# MiniUIOD_AP.net
KiCad netlist of a schematic drawn in Altium Designer
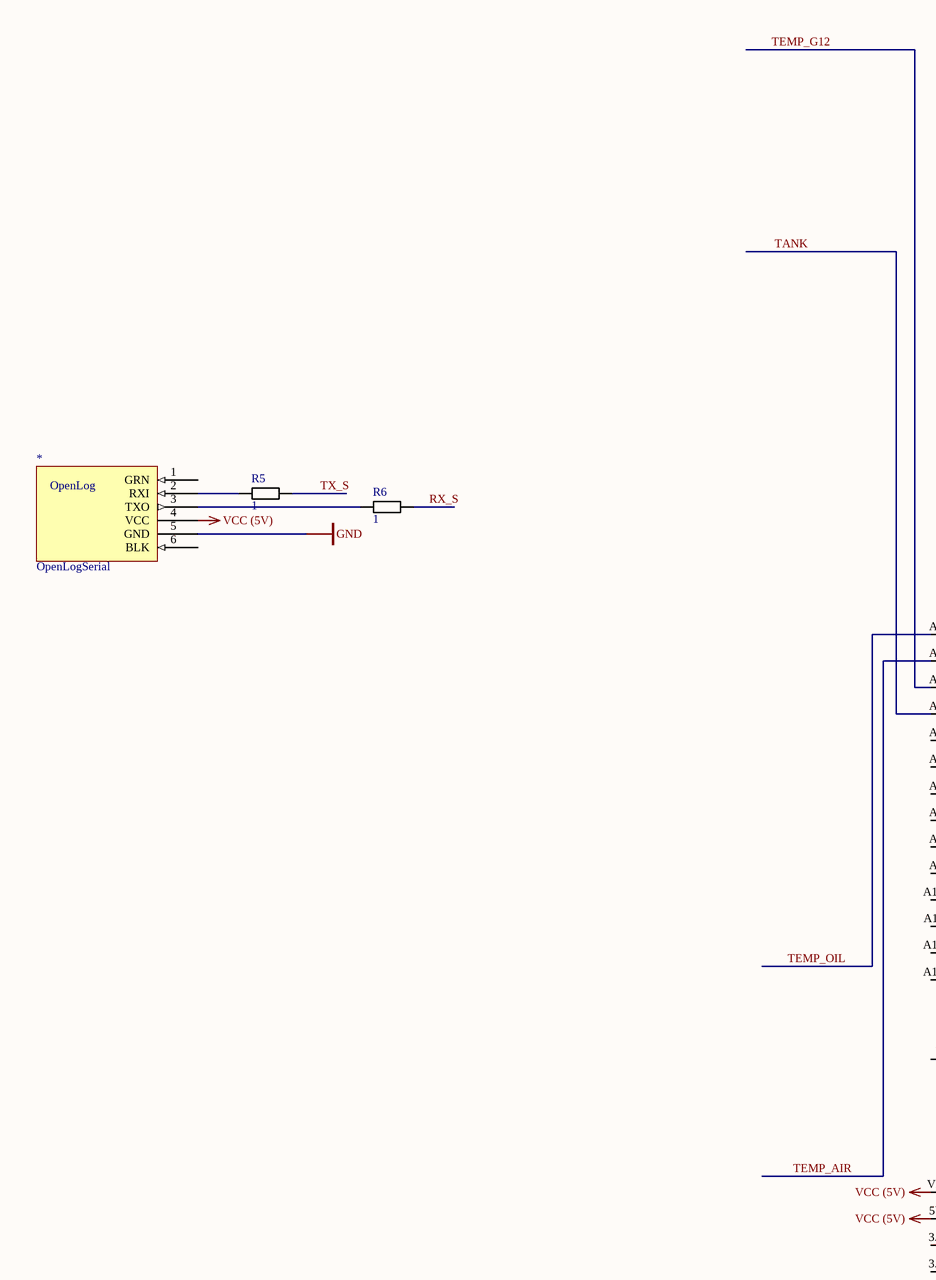
[diagram p0: MiniUIOD_AP.SchDoc, left]
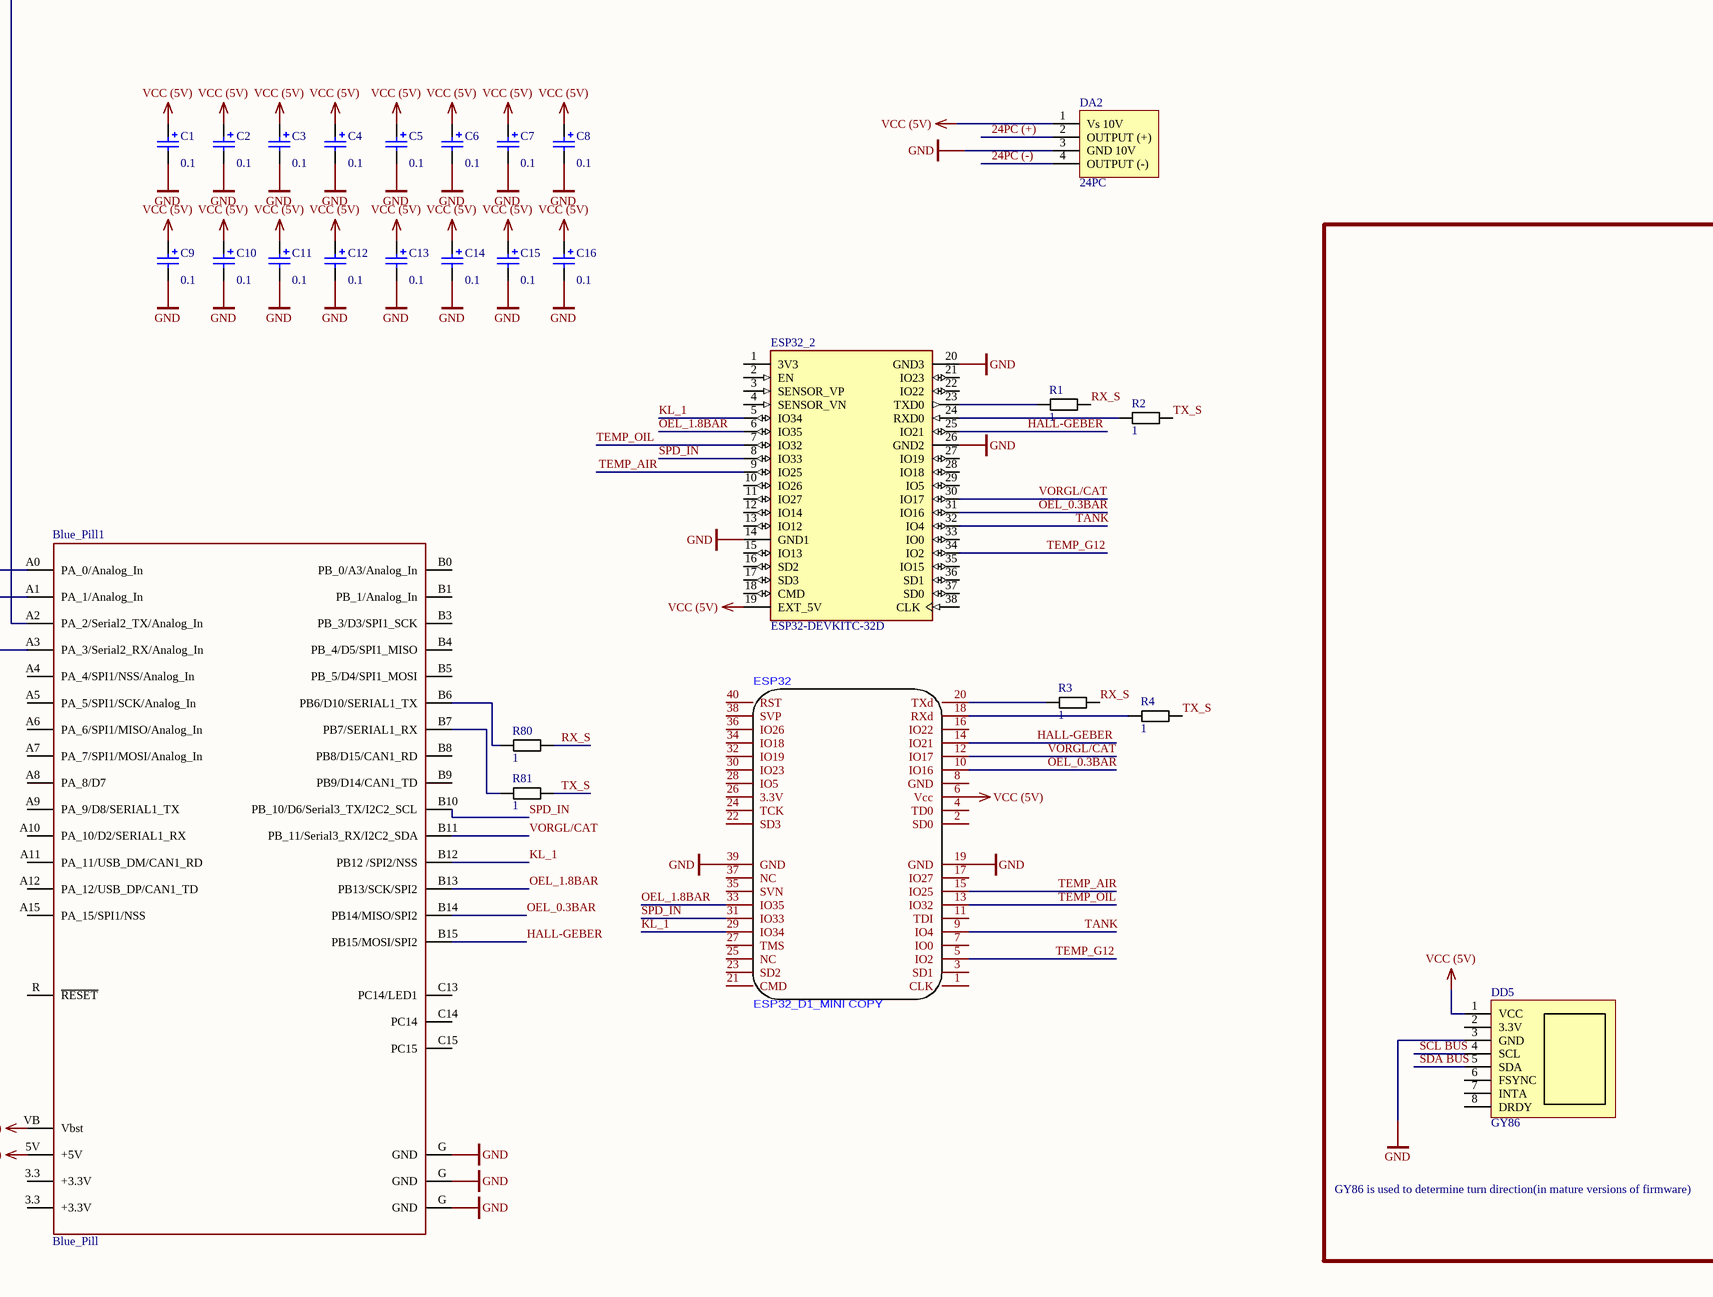
[diagram p1: MiniUIOD_AP.SchDoc, right]

(export (version "E")
  (design (tool "Eeschema 10.0.6"))
  (components
    (comp (ref "*")
      (value "OpenLogSerial")
      (footprint "OpenLogSerial")
      (libsource (lib "SN_NavBoard") (part "OpenLogSerial"))
    )
    (comp (ref "Blue_Pill1")
      (value "Blue_Pill")
      (footprint "BLUE_PILL")
      (libsource (lib "Digifiz_Schlib1") (part "BluePill"))
    )
    (comp (ref "C1")
      (value "0.1")
      (footprint "C0805")
      (description "Polarized Capacitor (Surface Mount)")
      (fields (field (name "Comment") "Cap Pol3") (field (name "PUBLISHER") "Altium Limited"))
      (libsource (lib "Driver_SchLib") (part "Cap Pol3"))
    )
    (comp (ref "C2")
      (value "0.1")
      (footprint "C0805")
      (description "Polarized Capacitor (Surface Mount)")
      (fields (field (name "Comment") "Cap Pol3") (field (name "PUBLISHER") "Altium Limited"))
      (libsource (lib "Driver_SchLib") (part "Cap Pol3"))
    )
    (comp (ref "C3")
      (value "0.1")
      (footprint "C0805")
      (description "Polarized Capacitor (Surface Mount)")
      (fields (field (name "Comment") "Cap Pol3") (field (name "PUBLISHER") "Altium Limited"))
      (libsource (lib "Driver_SchLib") (part "Cap Pol3"))
    )
    (comp (ref "C4")
      (value "0.1")
      (footprint "C0805")
      (description "Polarized Capacitor (Surface Mount)")
      (fields (field (name "Comment") "Cap Pol3") (field (name "PUBLISHER") "Altium Limited"))
      (libsource (lib "Driver_SchLib") (part "Cap Pol3"))
    )
    (comp (ref "C5")
      (value "0.1")
      (footprint "C0805")
      (description "Polarized Capacitor (Surface Mount)")
      (fields (field (name "Comment") "Cap Pol3") (field (name "PUBLISHER") "Altium Limited"))
      (libsource (lib "Driver_SchLib") (part "Cap Pol3"))
    )
    (comp (ref "C6")
      (value "0.1")
      (footprint "C0805")
      (description "Polarized Capacitor (Surface Mount)")
      (fields (field (name "Comment") "Cap Pol3") (field (name "PUBLISHER") "Altium Limited"))
      (libsource (lib "Driver_SchLib") (part "Cap Pol3"))
    )
    (comp (ref "C7")
      (value "0.1")
      (footprint "C0805")
      (description "Polarized Capacitor (Surface Mount)")
      (fields (field (name "Comment") "Cap Pol3") (field (name "PUBLISHER") "Altium Limited"))
      (libsource (lib "Driver_SchLib") (part "Cap Pol3"))
    )
    (comp (ref "C8")
      (value "0.1")
      (footprint "C0805")
      (description "Polarized Capacitor (Surface Mount)")
      (fields (field (name "Comment") "Cap Pol3") (field (name "PUBLISHER") "Altium Limited"))
      (libsource (lib "Driver_SchLib") (part "Cap Pol3"))
    )
    (comp (ref "C9")
      (value "0.1")
      (footprint "C0805")
      (description "Polarized Capacitor (Surface Mount)")
      (fields (field (name "Comment") "Cap Pol3") (field (name "PUBLISHER") "Altium Limited"))
      (libsource (lib "Driver_SchLib") (part "Cap Pol3"))
    )
    (comp (ref "C10")
      (value "0.1")
      (footprint "C0805")
      (description "Polarized Capacitor (Surface Mount)")
      (fields (field (name "Comment") "Cap Pol3") (field (name "PUBLISHER") "Altium Limited"))
      (libsource (lib "Driver_SchLib") (part "Cap Pol3"))
    )
    (comp (ref "C11")
      (value "0.1")
      (footprint "C0805")
      (description "Polarized Capacitor (Surface Mount)")
      (fields (field (name "Comment") "Cap Pol3") (field (name "PUBLISHER") "Altium Limited"))
      (libsource (lib "Driver_SchLib") (part "Cap Pol3"))
    )
    (comp (ref "C12")
      (value "0.1")
      (footprint "C0805")
      (description "Polarized Capacitor (Surface Mount)")
      (fields (field (name "Comment") "Cap Pol3") (field (name "PUBLISHER") "Altium Limited"))
      (libsource (lib "Driver_SchLib") (part "Cap Pol3"))
    )
    (comp (ref "C13")
      (value "0.1")
      (footprint "C0805")
      (description "Polarized Capacitor (Surface Mount)")
      (fields (field (name "Comment") "Cap Pol3") (field (name "PUBLISHER") "Altium Limited"))
      (libsource (lib "Driver_SchLib") (part "Cap Pol3"))
    )
    (comp (ref "C14")
      (value "0.1")
      (footprint "C0805")
      (description "Polarized Capacitor (Surface Mount)")
      (fields (field (name "Comment") "Cap Pol3") (field (name "PUBLISHER") "Altium Limited"))
      (libsource (lib "Driver_SchLib") (part "Cap Pol3"))
    )
    (comp (ref "C15")
      (value "0.1")
      (footprint "C0805")
      (description "Polarized Capacitor (Surface Mount)")
      (fields (field (name "Comment") "Cap Pol3") (field (name "PUBLISHER") "Altium Limited"))
      (libsource (lib "Driver_SchLib") (part "Cap Pol3"))
    )
    (comp (ref "C16")
      (value "0.1")
      (footprint "C0805")
      (description "Polarized Capacitor (Surface Mount)")
      (fields (field (name "Comment") "Cap Pol3") (field (name "PUBLISHER") "Altium Limited"))
      (libsource (lib "Driver_SchLib") (part "Cap Pol3"))
    )
    (comp (ref "DA2") (value "24PC") (footprint "24PC") (libsource (lib "Digifiz_Schlib1") (part "24PC")))
    (comp (ref "DD5")
      (value "GY86")
      (footprint "GY86_MODEL")
      (libsource (lib "Digifiz_Schlib1") (part "GY86_MODEL"))
    )
    (comp (ref "ESP32")
      (value "ESP32_D1_MINI COPY")
      (footprint "ESP32_MINI_MHET")
      (libsource (lib "MiniUIOD") (part "ESP32_D1_MINI COPY"))
    )
    (comp (ref "ESP32_2")
      (value "ESP32-DEVKITC-32D")
      (footprint "MODULE_ESP32-DEVKITC-32D")
      (description "EVAL BOARD FOR ESP-WROOM-32")
      (fields (field (name "MF") "Espressif Systems"))
      (libsource (lib "MiniUIOD") (part "ESP32-DEVKITC-32D"))
    )
    (comp (ref "R1")
      (value "1")
      (footprint "SMT0603/VISHAY")
      (libsource (lib "Digifiz_Schlib1") (part "CRCW0603_47"))
    )
    (comp (ref "R2")
      (value "1")
      (footprint "SMT0603/VISHAY")
      (libsource (lib "Digifiz_Schlib1") (part "CRCW0603_47"))
    )
    (comp (ref "R3")
      (value "1")
      (footprint "SMT0603/VISHAY")
      (libsource (lib "Digifiz_Schlib1") (part "CRCW0603_47"))
    )
    (comp (ref "R4")
      (value "1")
      (footprint "SMT0603/VISHAY")
      (libsource (lib "Digifiz_Schlib1") (part "CRCW0603_47"))
    )
    (comp (ref "R5")
      (value "1")
      (footprint "SMT0603/VISHAY")
      (libsource (lib "Digifiz_Schlib1") (part "CRCW0603_47"))
    )
    (comp (ref "R6")
      (value "1")
      (footprint "SMT0603/VISHAY")
      (libsource (lib "Digifiz_Schlib1") (part "CRCW0603_47"))
    )
    (comp (ref "R80")
      (value "1")
      (footprint "SMT0603/VISHAY")
      (libsource (lib "Digifiz_Schlib1") (part "CRCW0603_47"))
    )
    (comp (ref "R81")
      (value "1")
      (footprint "SMT0603/VISHAY")
      (libsource (lib "Digifiz_Schlib1") (part "CRCW0603_47"))
    )
  )
  (nets
    (net (code "1") (name "/24PC (+)") (class "Default")
      (node (ref "DA2") (pin "2") (pinfunction "OUTPUT_(+)_2") (pintype "passive"))
    )
    (net (code "2") (name "/24PC (-)") (class "Default")
      (node (ref "DA2") (pin "4") (pinfunction "OUTPUT_(-)_4") (pintype "passive"))
    )
    (net (code "3") (name "/HALL-GEBER") (class "Default")
      (node (ref "Blue_Pill1") (pin "B15") (pinfunction "PB15/MOSI/SPI2_B15") (pintype "passive"))
      (node (ref "ESP32") (pin "14") (pinfunction "IO21_14") (pintype "passive"))
      (node (ref "ESP32_2") (pin "25") (pinfunction "IO21_25") (pintype "bidirectional"))
    )
    (net (code "4") (name "/KL_1") (class "Default")
      (node (ref "Blue_Pill1") (pin "B12") (pinfunction "PB12_/SPI2/NSS_B12") (pintype "passive"))
      (node (ref "ESP32") (pin "29") (pinfunction "IO34_29") (pintype "passive"))
      (node (ref "ESP32_2") (pin "5") (pinfunction "IO34_5") (pintype "bidirectional"))
    )
    (net (code "5") (name "/OEL_0.3BAR") (class "Default")
      (node (ref "Blue_Pill1") (pin "B14") (pinfunction "PB14/MISO/SPI2_B14") (pintype "passive"))
      (node (ref "ESP32") (pin "10") (pinfunction "IO16_10") (pintype "passive"))
      (node (ref "ESP32_2") (pin "31") (pinfunction "IO16_31") (pintype "bidirectional"))
    )
    (net (code "6") (name "/OEL_1.8BAR") (class "Default")
      (node (ref "Blue_Pill1") (pin "B13") (pinfunction "PB13/SCK/SPI2_B13") (pintype "passive"))
      (node (ref "ESP32") (pin "33") (pinfunction "IO35_33") (pintype "passive"))
      (node (ref "ESP32_2") (pin "6") (pinfunction "IO35_6") (pintype "bidirectional"))
    )
    (net (code "7") (name "/RX_S") (class "Default")
      (node (ref "R1") (pin "1") (pinfunction "1_1") (pintype "passive"))
      (node (ref "R3") (pin "1") (pinfunction "1_1") (pintype "passive"))
      (node (ref "R6") (pin "1") (pinfunction "1_1") (pintype "passive"))
      (node (ref "R80") (pin "1") (pinfunction "1_1") (pintype "passive"))
    )
    (net (code "8") (name "/SCL BUS") (class "Default")
      (node (ref "DD5") (pin "4") (pinfunction "SCL_4") (pintype "passive"))
    )
    (net (code "9") (name "/SDA BUS") (class "Default")
      (node (ref "DD5") (pin "5") (pinfunction "SDA_5") (pintype "passive"))
    )
    (net (code "10") (name "/SPD_IN") (class "Default")
      (node (ref "Blue_Pill1") (pin "B10") (pinfunction "PB_10/D6/Serial3_TX/I2C2_SCL_B10") (pintype "passive"))
      (node (ref "ESP32") (pin "31") (pinfunction "IO33_31") (pintype "passive"))
      (node (ref "ESP32_2") (pin "8") (pinfunction "IO33_8") (pintype "bidirectional"))
    )
    (net (code "11") (name "/TANK") (class "Default")
      (node (ref "Blue_Pill1") (pin "A3") (pinfunction "PA_3/Serial2_RX/Analog_In_A3") (pintype "passive"))
      (node (ref "ESP32") (pin "9") (pinfunction "IO4_9") (pintype "passive"))
      (node (ref "ESP32_2") (pin "32") (pinfunction "IO4_32") (pintype "bidirectional"))
    )
    (net (code "12") (name "/TEMP_AIR") (class "Default")
      (node (ref "Blue_Pill1") (pin "A1") (pinfunction "PA_1/Analog_In_A1") (pintype "passive"))
      (node (ref "ESP32") (pin "15") (pinfunction "IO25_15") (pintype "passive"))
      (node (ref "ESP32_2") (pin "9") (pinfunction "IO25_9") (pintype "bidirectional"))
    )
    (net (code "13") (name "/TEMP_G12") (class "Default")
      (node (ref "Blue_Pill1") (pin "A2") (pinfunction "PA_2/Serial2_TX/Analog_In_A2") (pintype "passive"))
      (node (ref "ESP32") (pin "5") (pinfunction "IO2_5") (pintype "passive"))
      (node (ref "ESP32_2") (pin "34") (pinfunction "IO2_34") (pintype "bidirectional"))
    )
    (net (code "14") (name "/TEMP_OIL") (class "Default")
      (node (ref "Blue_Pill1") (pin "A0") (pinfunction "PA_0/Analog_In_A0") (pintype "passive"))
      (node (ref "ESP32") (pin "13") (pinfunction "IO32_13") (pintype "passive"))
      (node (ref "ESP32_2") (pin "7") (pinfunction "IO32_7") (pintype "bidirectional"))
    )
    (net (code "15") (name "/TX_S") (class "Default")
      (node (ref "R2") (pin "1") (pinfunction "1_1") (pintype "passive"))
      (node (ref "R4") (pin "1") (pinfunction "1_1") (pintype "passive"))
      (node (ref "R5") (pin "1") (pinfunction "1_1") (pintype "passive"))
      (node (ref "R81") (pin "1") (pinfunction "1_1") (pintype "passive"))
    )
    (net (code "16") (name "/VORGL{slash}CAT") (class "Default")
      (node (ref "Blue_Pill1") (pin "B11") (pinfunction "PB_11/Serial3_RX/I2C2_SDA_B11") (pintype "passive"))
      (node (ref "ESP32") (pin "12") (pinfunction "IO17_12") (pintype "passive"))
      (node (ref "ESP32_2") (pin "30") (pinfunction "IO17_30") (pintype "bidirectional"))
    )
    (net (code "17") (name "GND") (class "Default")
      (node (ref "*") (pin "5") (pinfunction "GND_5") (pintype "power_in"))
      (node (ref "Blue_Pill1") (pin "G") (pinfunction "GND_G") (pintype "passive"))
      (node (ref "C1") (pin "2") (pinfunction "2_2") (pintype "passive"))
      (node (ref "C10") (pin "2") (pinfunction "2_2") (pintype "passive"))
      (node (ref "C11") (pin "2") (pinfunction "2_2") (pintype "passive"))
      (node (ref "C12") (pin "2") (pinfunction "2_2") (pintype "passive"))
      (node (ref "C13") (pin "2") (pinfunction "2_2") (pintype "passive"))
      (node (ref "C14") (pin "2") (pinfunction "2_2") (pintype "passive"))
      (node (ref "C15") (pin "2") (pinfunction "2_2") (pintype "passive"))
      (node (ref "C16") (pin "2") (pinfunction "2_2") (pintype "passive"))
      (node (ref "C2") (pin "2") (pinfunction "2_2") (pintype "passive"))
      (node (ref "C3") (pin "2") (pinfunction "2_2") (pintype "passive"))
      (node (ref "C4") (pin "2") (pinfunction "2_2") (pintype "passive"))
      (node (ref "C5") (pin "2") (pinfunction "2_2") (pintype "passive"))
      (node (ref "C6") (pin "2") (pinfunction "2_2") (pintype "passive"))
      (node (ref "C7") (pin "2") (pinfunction "2_2") (pintype "passive"))
      (node (ref "C8") (pin "2") (pinfunction "2_2") (pintype "passive"))
      (node (ref "C9") (pin "2") (pinfunction "2_2") (pintype "passive"))
      (node (ref "DA2") (pin "3") (pinfunction "GND_10V_3") (pintype "passive"))
      (node (ref "DD5") (pin "3") (pinfunction "GND_3") (pintype "passive"))
      (node (ref "ESP32") (pin "19") (pinfunction "GND_19") (pintype "passive"))
      (node (ref "ESP32") (pin "39") (pinfunction "GND_39") (pintype "passive"))
      (node (ref "ESP32_2") (pin "14") (pinfunction "GND1_14") (pintype "power_in"))
      (node (ref "ESP32_2") (pin "20") (pinfunction "GND3_20") (pintype "power_in"))
      (node (ref "ESP32_2") (pin "26") (pinfunction "GND2_26") (pintype "power_in"))
    )
    (net (code "18") (name "Net-(*-RXI)") (class "Default")
      (node (ref "*") (pin "2") (pinfunction "RXI_2") (pintype "input"))
      (node (ref "R5") (pin "2") (pinfunction "2_2") (pintype "passive"))
    )
    (net (code "19") (name "Net-(*-TXO)") (class "Default")
      (node (ref "*") (pin "3") (pinfunction "TXO_3") (pintype "output"))
      (node (ref "R6") (pin "2") (pinfunction "2_2") (pintype "passive"))
    )
    (net (code "20") (name "Net-(Blue_Pill1-PB6{slash}D10{slash}SERIAL1_TX)") (class "Default")
      (node (ref "Blue_Pill1") (pin "B6") (pinfunction "PB6/D10/SERIAL1_TX_B6") (pintype "passive"))
      (node (ref "R80") (pin "2") (pinfunction "2_2") (pintype "passive"))
    )
    (net (code "21") (name "Net-(Blue_Pill1-PB7{slash}SERIAL1_RX)") (class "Default")
      (node (ref "Blue_Pill1") (pin "B7") (pinfunction "PB7/SERIAL1_RX_B7") (pintype "passive"))
      (node (ref "R81") (pin "2") (pinfunction "2_2") (pintype "passive"))
    )
    (net (code "22") (name "Net-(ESP32-RXd)") (class "Default")
      (node (ref "ESP32") (pin "18") (pinfunction "RXd_18") (pintype "passive"))
      (node (ref "R4") (pin "2") (pinfunction "2_2") (pintype "passive"))
    )
    (net (code "23") (name "Net-(ESP32-TXd)") (class "Default")
      (node (ref "ESP32") (pin "20") (pinfunction "TXd_20") (pintype "passive"))
      (node (ref "R3") (pin "2") (pinfunction "2_2") (pintype "passive"))
    )
    (net (code "24") (name "Net-(ESP32_2-RXD0)") (class "Default")
      (node (ref "ESP32_2") (pin "24") (pinfunction "RXD0_24") (pintype "input"))
      (node (ref "R2") (pin "2") (pinfunction "2_2") (pintype "passive"))
    )
    (net (code "25") (name "Net-(ESP32_2-TXD0)") (class "Default")
      (node (ref "ESP32_2") (pin "23") (pinfunction "TXD0_23") (pintype "output"))
      (node (ref "R1") (pin "2") (pinfunction "2_2") (pintype "passive"))
    )
    (net (code "26") (name "VCC (5V)") (class "Default")
      (node (ref "*") (pin "4") (pinfunction "VCC_4") (pintype "power_in"))
      (node (ref "Blue_Pill1") (pin "5V") (pinfunction "+5V_5V") (pintype "passive"))
      (node (ref "Blue_Pill1") (pin "VB") (pinfunction "Vbst_VB") (pintype "passive"))
      (node (ref "C1") (pin "1") (pinfunction "1_1") (pintype "passive"))
      (node (ref "C10") (pin "1") (pinfunction "1_1") (pintype "passive"))
      (node (ref "C11") (pin "1") (pinfunction "1_1") (pintype "passive"))
      (node (ref "C12") (pin "1") (pinfunction "1_1") (pintype "passive"))
      (node (ref "C13") (pin "1") (pinfunction "1_1") (pintype "passive"))
      (node (ref "C14") (pin "1") (pinfunction "1_1") (pintype "passive"))
      (node (ref "C15") (pin "1") (pinfunction "1_1") (pintype "passive"))
      (node (ref "C16") (pin "1") (pinfunction "1_1") (pintype "passive"))
      (node (ref "C2") (pin "1") (pinfunction "1_1") (pintype "passive"))
      (node (ref "C3") (pin "1") (pinfunction "1_1") (pintype "passive"))
      (node (ref "C4") (pin "1") (pinfunction "1_1") (pintype "passive"))
      (node (ref "C5") (pin "1") (pinfunction "1_1") (pintype "passive"))
      (node (ref "C6") (pin "1") (pinfunction "1_1") (pintype "passive"))
      (node (ref "C7") (pin "1") (pinfunction "1_1") (pintype "passive"))
      (node (ref "C8") (pin "1") (pinfunction "1_1") (pintype "passive"))
      (node (ref "C9") (pin "1") (pinfunction "1_1") (pintype "passive"))
      (node (ref "DA2") (pin "1") (pinfunction "Vs_10V_1") (pintype "passive"))
      (node (ref "DD5") (pin "1") (pinfunction "VCC_1") (pintype "passive"))
      (node (ref "ESP32") (pin "6") (pinfunction "Vcc_6") (pintype "passive"))
      (node (ref "ESP32_2") (pin "19") (pinfunction "EXT_5V_19") (pintype "power_in"))
    )
    (net (code "27") (name "unconnected-(*-BLK-Pad6)") (class "Default")
      (node (ref "*") (pin "6") (pinfunction "BLK_6") (pintype "input"))
    )
    (net (code "28") (name "unconnected-(*-GRN-Pad1)") (class "Default")
      (node (ref "*") (pin "1") (pinfunction "GRN_1") (pintype "input"))
    )
    (net (code "29") (name "unconnected-(Blue_Pill1-+3.3V-Pad3.3)") (class "Default")
      (node (ref "Blue_Pill1") (pin "3.3") (pinfunction "+3.3V_3.3") (pintype "passive"))
    )
    (net (code "30") (name "unconnected-(Blue_Pill1-+3.3V-Pad3.3)_1") (class "Default")
      (node (ref "Blue_Pill1") (pin "3.3") (pinfunction "+3.3V_3.3") (pintype "passive"))
    )
    (net (code "31") (name "unconnected-(Blue_Pill1-PA_4{slash}SPI1{slash}NSS{slash}Analog_In-PadA4)") (class "Default")
      (node (ref "Blue_Pill1") (pin "A4") (pinfunction "PA_4/SPI1/NSS/Analog_In_A4") (pintype "passive"))
    )
    (net (code "32") (name "unconnected-(Blue_Pill1-PA_5{slash}SPI1{slash}SCK{slash}Analog_In-PadA5)") (class "Default")
      (node (ref "Blue_Pill1") (pin "A5") (pinfunction "PA_5/SPI1/SCK/Analog_In_A5") (pintype "passive"))
    )
    (net (code "33") (name "unconnected-(Blue_Pill1-PA_6{slash}SPI1{slash}MISO{slash}Analog_In-PadA6)") (class "Default")
      (node (ref "Blue_Pill1") (pin "A6") (pinfunction "PA_6/SPI1/MISO/Analog_In_A6") (pintype "passive"))
    )
    (net (code "34") (name "unconnected-(Blue_Pill1-PA_7{slash}SPI1{slash}MOSI{slash}Analog_In-PadA7)") (class "Default")
      (node (ref "Blue_Pill1") (pin "A7") (pinfunction "PA_7/SPI1/MOSI/Analog_In_A7") (pintype "passive"))
    )
    (net (code "35") (name "unconnected-(Blue_Pill1-PA_8{slash}D7-PadA8)") (class "Default")
      (node (ref "Blue_Pill1") (pin "A8") (pinfunction "PA_8/D7_A8") (pintype "passive"))
    )
    (net (code "36") (name "unconnected-(Blue_Pill1-PA_9{slash}D8{slash}SERIAL1_TX-PadA9)") (class "Default")
      (node (ref "Blue_Pill1") (pin "A9") (pinfunction "PA_9/D8/SERIAL1_TX_A9") (pintype "passive"))
    )
    (net (code "37") (name "unconnected-(Blue_Pill1-PA_10{slash}D2{slash}SERIAL1_RX-PadA10)") (class "Default")
      (node (ref "Blue_Pill1") (pin "A10") (pinfunction "PA_10/D2/SERIAL1_RX_A10") (pintype "passive"))
    )
    (net (code "38") (name "unconnected-(Blue_Pill1-PA_11{slash}USB_DM{slash}CAN1_RD-PadA11)") (class "Default")
      (node (ref "Blue_Pill1") (pin "A11") (pinfunction "PA_11/USB_DM/CAN1_RD_A11") (pintype "passive"))
    )
    (net (code "39") (name "unconnected-(Blue_Pill1-PA_12{slash}USB_DP{slash}CAN1_TD-PadA12)") (class "Default")
      (node (ref "Blue_Pill1") (pin "A12") (pinfunction "PA_12/USB_DP/CAN1_TD_A12") (pintype "passive"))
    )
    (net (code "40") (name "unconnected-(Blue_Pill1-PA_15{slash}SPI1{slash}NSS-PadA15)") (class "Default")
      (node (ref "Blue_Pill1") (pin "A15") (pinfunction "PA_15/SPI1/NSS_A15") (pintype "passive"))
    )
    (net (code "41") (name "unconnected-(Blue_Pill1-PB8{slash}D15{slash}CAN1_RD-PadB8)") (class "Default")
      (node (ref "Blue_Pill1") (pin "B8") (pinfunction "PB8/D15/CAN1_RD_B8") (pintype "passive"))
    )
    (net (code "42") (name "unconnected-(Blue_Pill1-PB9{slash}D14{slash}CAN1_TD-PadB9)") (class "Default")
      (node (ref "Blue_Pill1") (pin "B9") (pinfunction "PB9/D14/CAN1_TD_B9") (pintype "passive"))
    )
    (net (code "43") (name "unconnected-(Blue_Pill1-PB_0{slash}A3{slash}Analog_In-PadB0)") (class "Default")
      (node (ref "Blue_Pill1") (pin "B0") (pinfunction "PB_0/A3/Analog_In_B0") (pintype "passive"))
    )
    (net (code "44") (name "unconnected-(Blue_Pill1-PB_1{slash}Analog_In-PadB1)") (class "Default")
      (node (ref "Blue_Pill1") (pin "B1") (pinfunction "PB_1/Analog_In_B1") (pintype "passive"))
    )
    (net (code "45") (name "unconnected-(Blue_Pill1-PB_3{slash}D3{slash}SPI1_SCK-PadB3)") (class "Default")
      (node (ref "Blue_Pill1") (pin "B3") (pinfunction "PB_3/D3/SPI1_SCK_B3") (pintype "passive"))
    )
    (net (code "46") (name "unconnected-(Blue_Pill1-PB_4{slash}D5{slash}SPI1_MISO-PadB4)") (class "Default")
      (node (ref "Blue_Pill1") (pin "B4") (pinfunction "PB_4/D5/SPI1_MISO_B4") (pintype "passive"))
    )
    (net (code "47") (name "unconnected-(Blue_Pill1-PB_5{slash}D4{slash}SPI1_MOSI-PadB5)") (class "Default")
      (node (ref "Blue_Pill1") (pin "B5") (pinfunction "PB_5/D4/SPI1_MOSI_B5") (pintype "passive"))
    )
    (net (code "48") (name "unconnected-(Blue_Pill1-PC14-PadC14)") (class "Default")
      (node (ref "Blue_Pill1") (pin "C14") (pinfunction "PC14_C14") (pintype "passive"))
    )
    (net (code "49") (name "unconnected-(Blue_Pill1-PC14{slash}LED1-PadC13)") (class "Default")
      (node (ref "Blue_Pill1") (pin "C13") (pinfunction "PC14/LED1_C13") (pintype "passive"))
    )
    (net (code "50") (name "unconnected-(Blue_Pill1-PC15-PadC15)") (class "Default")
      (node (ref "Blue_Pill1") (pin "C15") (pinfunction "PC15_C15") (pintype "passive"))
    )
    (net (code "51") (name "unconnected-(Blue_Pill1-~{RESET}-PadR)") (class "Default")
      (node (ref "Blue_Pill1") (pin "R") (pinfunction "~{RESET}_R") (pintype "passive"))
    )
    (net (code "52") (name "unconnected-(DD5-3.3V-Pad2)") (class "Default")
      (node (ref "DD5") (pin "2") (pinfunction "3.3V_2") (pintype "passive"))
    )
    (net (code "53") (name "unconnected-(DD5-DRDY-Pad8)") (class "Default")
      (node (ref "DD5") (pin "8") (pinfunction "DRDY_8") (pintype "passive"))
    )
    (net (code "54") (name "unconnected-(DD5-FSYNC-Pad6)") (class "Default")
      (node (ref "DD5") (pin "6") (pinfunction "FSYNC_6") (pintype "passive"))
    )
    (net (code "55") (name "unconnected-(DD5-INTA-Pad7)") (class "Default")
      (node (ref "DD5") (pin "7") (pinfunction "INTA_7") (pintype "passive"))
    )
    (net (code "56") (name "unconnected-(ESP32-3.3V-Pad26)") (class "Default")
      (node (ref "ESP32") (pin "26") (pinfunction "3.3V_26") (pintype "passive"))
    )
    (net (code "57") (name "unconnected-(ESP32-CLK-Pad1)") (class "Default")
      (node (ref "ESP32") (pin "1") (pinfunction "CLK_1") (pintype "passive"))
    )
    (net (code "58") (name "unconnected-(ESP32-CMD-Pad21)") (class "Default")
      (node (ref "ESP32") (pin "21") (pinfunction "CMD_21") (pintype "passive"))
    )
    (net (code "59") (name "unconnected-(ESP32-GND-Pad8)") (class "Default")
      (node (ref "ESP32") (pin "8") (pinfunction "GND_8") (pintype "passive"))
    )
    (net (code "60") (name "unconnected-(ESP32-IO0-Pad7)") (class "Default")
      (node (ref "ESP32") (pin "7") (pinfunction "IO0_7") (pintype "passive"))
    )
    (net (code "61") (name "unconnected-(ESP32-IO5-Pad28)") (class "Default")
      (node (ref "ESP32") (pin "28") (pinfunction "IO5_28") (pintype "passive"))
    )
    (net (code "62") (name "unconnected-(ESP32-IO18-Pad34)") (class "Default")
      (node (ref "ESP32") (pin "34") (pinfunction "IO18_34") (pintype "passive"))
    )
    (net (code "63") (name "unconnected-(ESP32-IO19-Pad32)") (class "Default")
      (node (ref "ESP32") (pin "32") (pinfunction "IO19_32") (pintype "passive"))
    )
    (net (code "64") (name "unconnected-(ESP32-IO22-Pad16)") (class "Default")
      (node (ref "ESP32") (pin "16") (pinfunction "IO22_16") (pintype "passive"))
    )
    (net (code "65") (name "unconnected-(ESP32-IO23-Pad30)") (class "Default")
      (node (ref "ESP32") (pin "30") (pinfunction "IO23_30") (pintype "passive"))
    )
    (net (code "66") (name "unconnected-(ESP32-IO26-Pad36)") (class "Default")
      (node (ref "ESP32") (pin "36") (pinfunction "IO26_36") (pintype "passive"))
    )
    (net (code "67") (name "unconnected-(ESP32-IO27-Pad17)") (class "Default")
      (node (ref "ESP32") (pin "17") (pinfunction "IO27_17") (pintype "passive"))
    )
    (net (code "68") (name "unconnected-(ESP32-NC-Pad25)") (class "Default")
      (node (ref "ESP32") (pin "25") (pinfunction "NC_25") (pintype "passive"))
    )
    (net (code "69") (name "unconnected-(ESP32-NC-Pad37)") (class "Default")
      (node (ref "ESP32") (pin "37") (pinfunction "NC_37") (pintype "passive"))
    )
    (net (code "70") (name "unconnected-(ESP32-RST-Pad40)") (class "Default")
      (node (ref "ESP32") (pin "40") (pinfunction "RST_40") (pintype "passive"))
    )
    (net (code "71") (name "unconnected-(ESP32-SD0-Pad2)") (class "Default")
      (node (ref "ESP32") (pin "2") (pinfunction "SD0_2") (pintype "passive"))
    )
    (net (code "72") (name "unconnected-(ESP32-SD1-Pad3)") (class "Default")
      (node (ref "ESP32") (pin "3") (pinfunction "SD1_3") (pintype "passive"))
    )
    (net (code "73") (name "unconnected-(ESP32-SD2-Pad23)") (class "Default")
      (node (ref "ESP32") (pin "23") (pinfunction "SD2_23") (pintype "passive"))
    )
    (net (code "74") (name "unconnected-(ESP32-SD3-Pad22)") (class "Default")
      (node (ref "ESP32") (pin "22") (pinfunction "SD3_22") (pintype "passive"))
    )
    (net (code "75") (name "unconnected-(ESP32-SVN-Pad35)") (class "Default")
      (node (ref "ESP32") (pin "35") (pinfunction "SVN_35") (pintype "passive"))
    )
    (net (code "76") (name "unconnected-(ESP32-SVP-Pad38)") (class "Default")
      (node (ref "ESP32") (pin "38") (pinfunction "SVP_38") (pintype "passive"))
    )
    (net (code "77") (name "unconnected-(ESP32-TCK-Pad24)") (class "Default")
      (node (ref "ESP32") (pin "24") (pinfunction "TCK_24") (pintype "passive"))
    )
    (net (code "78") (name "unconnected-(ESP32-TD0-Pad4)") (class "Default")
      (node (ref "ESP32") (pin "4") (pinfunction "TD0_4") (pintype "passive"))
    )
    (net (code "79") (name "unconnected-(ESP32-TDI-Pad11)") (class "Default")
      (node (ref "ESP32") (pin "11") (pinfunction "TDI_11") (pintype "passive"))
    )
    (net (code "80") (name "unconnected-(ESP32-TMS-Pad27)") (class "Default")
      (node (ref "ESP32") (pin "27") (pinfunction "TMS_27") (pintype "passive"))
    )
    (net (code "81") (name "unconnected-(ESP32_2-3V3-Pad1)") (class "Default")
      (node (ref "ESP32_2") (pin "1") (pinfunction "3V3_1") (pintype "power_in"))
    )
    (net (code "82") (name "unconnected-(ESP32_2-CLK-Pad38)") (class "Default")
      (node (ref "ESP32_2") (pin "38") (pinfunction "CLK_38") (pintype "input"))
    )
    (net (code "83") (name "unconnected-(ESP32_2-CMD-Pad18)") (class "Default")
      (node (ref "ESP32_2") (pin "18") (pinfunction "CMD_18") (pintype "bidirectional"))
    )
    (net (code "84") (name "unconnected-(ESP32_2-EN-Pad2)") (class "Default")
      (node (ref "ESP32_2") (pin "2") (pinfunction "EN_2") (pintype "input"))
    )
    (net (code "85") (name "unconnected-(ESP32_2-IO0-Pad33)") (class "Default")
      (node (ref "ESP32_2") (pin "33") (pinfunction "IO0_33") (pintype "bidirectional"))
    )
    (net (code "86") (name "unconnected-(ESP32_2-IO5-Pad29)") (class "Default")
      (node (ref "ESP32_2") (pin "29") (pinfunction "IO5_29") (pintype "bidirectional"))
    )
    (net (code "87") (name "unconnected-(ESP32_2-IO12-Pad13)") (class "Default")
      (node (ref "ESP32_2") (pin "13") (pinfunction "IO12_13") (pintype "bidirectional"))
    )
    (net (code "88") (name "unconnected-(ESP32_2-IO13-Pad15)") (class "Default")
      (node (ref "ESP32_2") (pin "15") (pinfunction "IO13_15") (pintype "bidirectional"))
    )
    (net (code "89") (name "unconnected-(ESP32_2-IO14-Pad12)") (class "Default")
      (node (ref "ESP32_2") (pin "12") (pinfunction "IO14_12") (pintype "bidirectional"))
    )
    (net (code "90") (name "unconnected-(ESP32_2-IO15-Pad35)") (class "Default")
      (node (ref "ESP32_2") (pin "35") (pinfunction "IO15_35") (pintype "bidirectional"))
    )
    (net (code "91") (name "unconnected-(ESP32_2-IO18-Pad28)") (class "Default")
      (node (ref "ESP32_2") (pin "28") (pinfunction "IO18_28") (pintype "bidirectional"))
    )
    (net (code "92") (name "unconnected-(ESP32_2-IO19-Pad27)") (class "Default")
      (node (ref "ESP32_2") (pin "27") (pinfunction "IO19_27") (pintype "bidirectional"))
    )
    (net (code "93") (name "unconnected-(ESP32_2-IO22-Pad22)") (class "Default")
      (node (ref "ESP32_2") (pin "22") (pinfunction "IO22_22") (pintype "bidirectional"))
    )
    (net (code "94") (name "unconnected-(ESP32_2-IO23-Pad21)") (class "Default")
      (node (ref "ESP32_2") (pin "21") (pinfunction "IO23_21") (pintype "bidirectional"))
    )
    (net (code "95") (name "unconnected-(ESP32_2-IO26-Pad10)") (class "Default")
      (node (ref "ESP32_2") (pin "10") (pinfunction "IO26_10") (pintype "bidirectional"))
    )
    (net (code "96") (name "unconnected-(ESP32_2-IO27-Pad11)") (class "Default")
      (node (ref "ESP32_2") (pin "11") (pinfunction "IO27_11") (pintype "bidirectional"))
    )
    (net (code "97") (name "unconnected-(ESP32_2-SD0-Pad37)") (class "Default")
      (node (ref "ESP32_2") (pin "37") (pinfunction "SD0_37") (pintype "bidirectional"))
    )
    (net (code "98") (name "unconnected-(ESP32_2-SD1-Pad36)") (class "Default")
      (node (ref "ESP32_2") (pin "36") (pinfunction "SD1_36") (pintype "bidirectional"))
    )
    (net (code "99") (name "unconnected-(ESP32_2-SD2-Pad16)") (class "Default")
      (node (ref "ESP32_2") (pin "16") (pinfunction "SD2_16") (pintype "bidirectional"))
    )
    (net (code "100") (name "unconnected-(ESP32_2-SD3-Pad17)") (class "Default")
      (node (ref "ESP32_2") (pin "17") (pinfunction "SD3_17") (pintype "bidirectional"))
    )
    (net (code "101") (name "unconnected-(ESP32_2-SENSOR_VN-Pad4)") (class "Default")
      (node (ref "ESP32_2") (pin "4") (pinfunction "SENSOR_VN_4") (pintype "input"))
    )
    (net (code "102") (name "unconnected-(ESP32_2-SENSOR_VP-Pad3)") (class "Default")
      (node (ref "ESP32_2") (pin "3") (pinfunction "SENSOR_VP_3") (pintype "input"))
    )
  )
)
